# sdr_3157.net
KiCad netlist of a schematic drawn in EAGLE
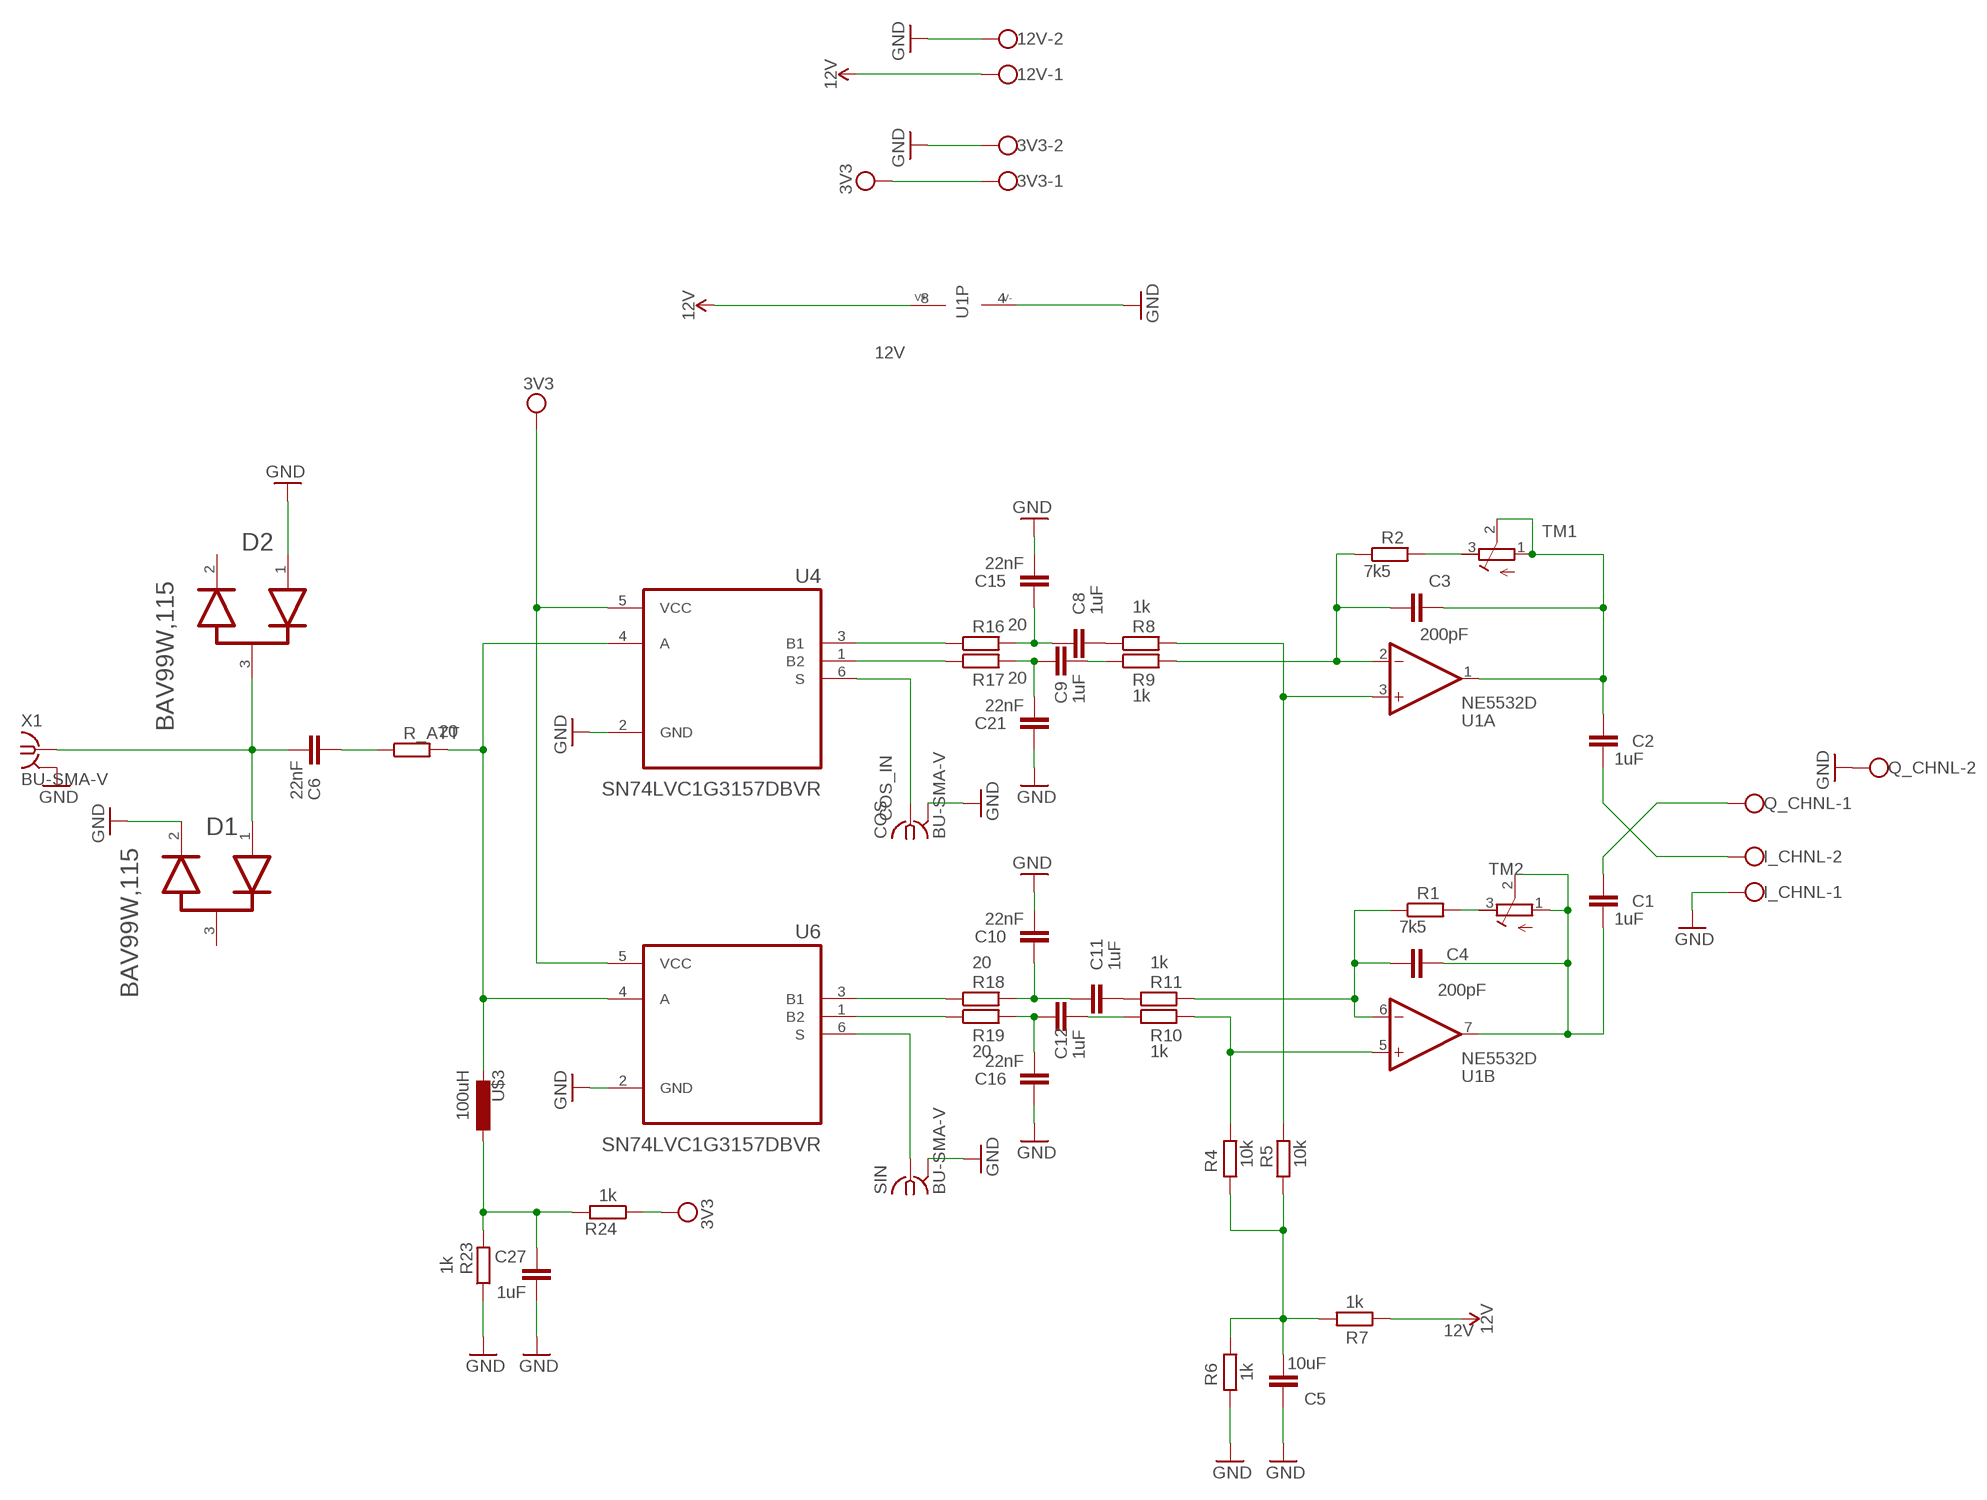
[diagram p0: schematic, sheet 1]

(export (version "E")
  (design (tool "Eeschema 10.0.6"))
  (components
    (comp (ref "3V3")
      (value "W237-102")
      (footprint "eagle-import:W237-102")
      (fields (field (name "MPN") "237-102"))
      (libsource (lib "eagle-import") (part "W237-102"))
    )
    (comp (ref "12V")
      (value "W237-102")
      (footprint "eagle-import:W237-102")
      (fields (field (name "MPN") "237-102"))
      (libsource (lib "eagle-import") (part "W237-102"))
    )
    (comp (ref "C1")
      (value "1uF")
      (footprint "eagle-import:C050-045X075")
      (libsource (lib "eagle-import") (part "C-EU050-045X075"))
    )
    (comp (ref "C2")
      (value "1uF")
      (footprint "eagle-import:C050-045X075")
      (libsource (lib "eagle-import") (part "C-EU050-045X075"))
    )
    (comp (ref "C3")
      (value "200pF")
      (footprint "eagle-import:C050-045X075")
      (libsource (lib "eagle-import") (part "C-EU050-045X075"))
    )
    (comp (ref "C4")
      (value "200pF")
      (footprint "eagle-import:C050-045X075")
      (libsource (lib "eagle-import") (part "C-EU050-045X075"))
    )
    (comp (ref "C5")
      (value "10uF")
      (footprint "eagle-import:C0805")
      (libsource (lib "eagle-import") (part "C-EUC0805"))
    )
    (comp (ref "C6")
      (value "22nF")
      (footprint "eagle-import:C1206K")
      (libsource (lib "eagle-import") (part "C-EUC1206K"))
    )
    (comp (ref "C8")
      (value "1uF")
      (footprint "eagle-import:C0805")
      (libsource (lib "eagle-import") (part "C-EUC0805"))
    )
    (comp (ref "C9")
      (value "1uF")
      (footprint "eagle-import:C0805")
      (libsource (lib "eagle-import") (part "C-EUC0805"))
    )
    (comp (ref "C10")
      (value "22nF")
      (footprint "eagle-import:C0805")
      (libsource (lib "eagle-import") (part "C-EUC0805"))
    )
    (comp (ref "C11")
      (value "1uF")
      (footprint "eagle-import:C0805")
      (libsource (lib "eagle-import") (part "C-EUC0805"))
    )
    (comp (ref "C12")
      (value "1uF")
      (footprint "eagle-import:C0805")
      (libsource (lib "eagle-import") (part "C-EUC0805"))
    )
    (comp (ref "C15")
      (value "22nF")
      (footprint "eagle-import:C0805")
      (libsource (lib "eagle-import") (part "C-EUC0805"))
    )
    (comp (ref "C16")
      (value "22nF")
      (footprint "eagle-import:C0805")
      (libsource (lib "eagle-import") (part "C-EUC0805"))
    )
    (comp (ref "C21")
      (value "22nF")
      (footprint "eagle-import:C0805")
      (libsource (lib "eagle-import") (part "C-EUC0805"))
    )
    (comp (ref "C27")
      (value "1uF")
      (footprint "eagle-import:C0805")
      (libsource (lib "eagle-import") (part "C-EUC0805"))
    )
    (comp (ref "COS")
      (value "BU-SMA-V")
      (footprint "eagle-import:BU-SMA-V")
      (libsource (lib "eagle-import") (part "BU-SMA-V"))
    )
    (comp (ref "D1")
      (value "NEXPERIA_BAV99W,115NEXPERIA_BAV99W,115_0_0")
      (footprint "eagle-import:NEXPERIA_BAV99W,115_0")
      (fields
        (field (name "3DS_PART_NUMBER") "412-00001")
        (field (name "DIGIKEY_PART_NUMBER") "1727-2915-1-ND")
        (field (name "MF") "Nexperia")
      )
      (libsource (lib "eagle-import") (part "NEXPERIA_BAV99W,115NEXPERIA_BAV99W,115_0_0"))
    )
    (comp (ref "D2")
      (value "NEXPERIA_BAV99W,115NEXPERIA_BAV99W,115_0_0")
      (footprint "eagle-import:NEXPERIA_BAV99W,115_0")
      (fields
        (field (name "3DS_PART_NUMBER") "412-00001")
        (field (name "DIGIKEY_PART_NUMBER") "1727-2915-1-ND")
        (field (name "MF") "Nexperia")
      )
      (libsource (lib "eagle-import") (part "NEXPERIA_BAV99W,115NEXPERIA_BAV99W,115_0_0"))
    )
    (comp (ref "I_CHNL")
      (value "W237-102")
      (footprint "eagle-import:W237-102")
      (fields (field (name "MPN") "237-102"))
      (libsource (lib "eagle-import") (part "W237-102"))
    )
    (comp (ref "Q_CHNL")
      (value "W237-102")
      (footprint "eagle-import:W237-102")
      (fields (field (name "MPN") "237-102"))
      (libsource (lib "eagle-import") (part "W237-102"))
    )
    (comp (ref "R1")
      (value "7k5")
      (footprint "eagle-import:R0805")
      (libsource (lib "eagle-import") (part "R-EU_R0805"))
    )
    (comp (ref "R2")
      (value "7k5")
      (footprint "eagle-import:R0805")
      (libsource (lib "eagle-import") (part "R-EU_R0805"))
    )
    (comp (ref "R4")
      (value "10k")
      (footprint "eagle-import:M0805")
      (libsource (lib "eagle-import") (part "R-EU_M0805"))
    )
    (comp (ref "R5")
      (value "10k")
      (footprint "eagle-import:R0805")
      (libsource (lib "eagle-import") (part "R-EU_R0805"))
    )
    (comp (ref "R6")
      (value "1k")
      (footprint "eagle-import:M0805")
      (libsource (lib "eagle-import") (part "R-EU_M0805"))
    )
    (comp (ref "R7")
      (value "1k")
      (footprint "eagle-import:M0805")
      (libsource (lib "eagle-import") (part "R-EU_M0805"))
    )
    (comp (ref "R8")
      (value "1k")
      (footprint "eagle-import:R0805")
      (libsource (lib "eagle-import") (part "R-EU_R0805"))
    )
    (comp (ref "R9")
      (value "1k")
      (footprint "eagle-import:R0805")
      (libsource (lib "eagle-import") (part "R-EU_R0805"))
    )
    (comp (ref "R10")
      (value "1k")
      (footprint "eagle-import:R0805")
      (libsource (lib "eagle-import") (part "R-EU_R0805"))
    )
    (comp (ref "R11")
      (value "1k")
      (footprint "eagle-import:M0805")
      (libsource (lib "eagle-import") (part "R-EU_M0805"))
    )
    (comp (ref "R16")
      (value "20")
      (footprint "eagle-import:R0805")
      (libsource (lib "eagle-import") (part "R-EU_R0805"))
    )
    (comp (ref "R17")
      (value "20")
      (footprint "eagle-import:R0805")
      (libsource (lib "eagle-import") (part "R-EU_R0805"))
    )
    (comp (ref "R18")
      (value "20")
      (footprint "eagle-import:R0805")
      (libsource (lib "eagle-import") (part "R-EU_R0805"))
    )
    (comp (ref "R19")
      (value "20")
      (footprint "eagle-import:R0805")
      (libsource (lib "eagle-import") (part "R-EU_R0805"))
    )
    (comp (ref "R23")
      (value "1k")
      (footprint "eagle-import:R0805")
      (libsource (lib "eagle-import") (part "R-EU_R0805"))
    )
    (comp (ref "R24")
      (value "1k")
      (footprint "eagle-import:R0805")
      (libsource (lib "eagle-import") (part "R-EU_R0805"))
    )
    (comp (ref "R_ATT")
      (value "20")
      (footprint "eagle-import:R1210")
      (libsource (lib "eagle-import") (part "R-EU_R1210"))
    )
    (comp (ref "SIN")
      (value "BU-SMA-V")
      (footprint "eagle-import:BU-SMA-V")
      (libsource (lib "eagle-import") (part "BU-SMA-V"))
    )
    (comp (ref "TM1")
      (value "5k")
      (footprint "eagle-import:RTRIM3296W")
      (libsource (lib "eagle-import") (part "R-TRIMM3296W"))
    )
    (comp (ref "TM2")
      (value "5k")
      (footprint "eagle-import:RTRIM3296W")
      (libsource (lib "eagle-import") (part "R-TRIMM3296W"))
    )
    (comp (ref "U$3")
      (value "100uH")
      (footprint "eagle-import:0207_10")
      (libsource (lib "eagle-import") (part "L-EU0207/10"))
    )
    (comp (ref "U1")
      (value "NE5532D")
      (footprint "eagle-import:SO08")
      (libsource (lib "eagle-import") (part "NE5532D"))
    )
    (comp (ref "U4")
      (value "SN74LVC1G3157DBVR")
      (footprint "eagle-import:SOT95P280X145-6N")
      (fields (field (name "MF") "Texas Instruments"))
      (libsource (lib "eagle-import") (part "SN74LVC1G3157DBVR"))
    )
    (comp (ref "U6")
      (value "SN74LVC1G3157DBVR")
      (footprint "eagle-import:SOT95P280X145-6N")
      (fields (field (name "MF") "Texas Instruments"))
      (libsource (lib "eagle-import") (part "SN74LVC1G3157DBVR"))
    )
    (comp (ref "X1")
      (value "BU-SMA-V")
      (footprint "eagle-import:BU-SMA-V")
      (libsource (lib "eagle-import") (part "BU-SMA-V"))
    )
  )
  (nets
    (net (code "1") (name "/COS_IN") (class "Default")
      (node (ref "COS") (pin "1") (pinfunction "1_1") (pintype "passive"))
      (node (ref "U4") (pin "6") (pinfunction "S_6") (pintype "input"))
    )
    (net (code "2") (name "3V3") (class "Default")
      (node (ref "3V3") (pin "1") (pinfunction "KL_1") (pintype "passive"))
      (node (ref "R24") (pin "1") (pinfunction "1_1") (pintype "passive"))
      (node (ref "U4") (pin "5") (pinfunction "VCC_5") (pintype "power_in"))
      (node (ref "U6") (pin "5") (pinfunction "VCC_5") (pintype "power_in"))
    )
    (net (code "3") (name "12V") (class "Default")
      (node (ref "12V") (pin "1") (pinfunction "KL_1") (pintype "passive"))
      (node (ref "R7") (pin "1") (pinfunction "1_1") (pintype "passive"))
      (node (ref "U1") (pin "8") (pinfunction "V+_8") (pintype "power_in"))
    )
    (net (code "4") (name "GND") (class "Default")
      (node (ref "12V") (pin "2") (pinfunction "KL_2") (pintype "passive"))
      (node (ref "3V3") (pin "2") (pinfunction "KL_2") (pintype "passive"))
      (node (ref "C10") (pin "2") (pinfunction "2_2") (pintype "passive"))
      (node (ref "C15") (pin "2") (pinfunction "2_2") (pintype "passive"))
      (node (ref "C16") (pin "1") (pinfunction "1_1") (pintype "passive"))
      (node (ref "C21") (pin "1") (pinfunction "1_1") (pintype "passive"))
      (node (ref "C27") (pin "1") (pinfunction "1_1") (pintype "passive"))
      (node (ref "C5") (pin "1") (pinfunction "1_1") (pintype "passive"))
      (node (ref "COS") (pin "2") (pinfunction "2_2") (pintype "passive"))
      (node (ref "COS") (pin "3") (pinfunction "2_3") (pintype "passive"))
      (node (ref "COS") (pin "4") (pinfunction "2_4") (pintype "passive"))
      (node (ref "COS") (pin "5") (pinfunction "2_5") (pintype "passive"))
      (node (ref "D1") (pin "2") (pinfunction "2_CATHODE_2") (pintype "passive"))
      (node (ref "D2") (pin "1") (pinfunction "1_ANODE_1") (pintype "passive"))
      (node (ref "I_CHNL") (pin "1") (pinfunction "KL_1") (pintype "passive"))
      (node (ref "Q_CHNL") (pin "2") (pinfunction "KL_2") (pintype "passive"))
      (node (ref "R23") (pin "1") (pinfunction "1_1") (pintype "passive"))
      (node (ref "R6") (pin "1") (pinfunction "1_1") (pintype "passive"))
      (node (ref "SIN") (pin "2") (pinfunction "2_2") (pintype "passive"))
      (node (ref "SIN") (pin "3") (pinfunction "2_3") (pintype "passive"))
      (node (ref "SIN") (pin "4") (pinfunction "2_4") (pintype "passive"))
      (node (ref "SIN") (pin "5") (pinfunction "2_5") (pintype "passive"))
      (node (ref "U1") (pin "4") (pinfunction "V-_4") (pintype "power_in"))
      (node (ref "U4") (pin "2") (pinfunction "GND_2") (pintype "power_in"))
      (node (ref "U6") (pin "2") (pinfunction "GND_2") (pintype "power_in"))
      (node (ref "X1") (pin "2") (pinfunction "2_2") (pintype "passive"))
      (node (ref "X1") (pin "3") (pinfunction "2_3") (pintype "passive"))
      (node (ref "X1") (pin "4") (pinfunction "2_4") (pintype "passive"))
      (node (ref "X1") (pin "5") (pinfunction "2_5") (pintype "passive"))
    )
    (net (code "5") (name "Net-(C5-Pad2)") (class "Default")
      (node (ref "C5") (pin "2") (pinfunction "2_2") (pintype "passive"))
      (node (ref "R4") (pin "1") (pinfunction "1_1") (pintype "passive"))
      (node (ref "R5") (pin "1") (pinfunction "1_1") (pintype "passive"))
      (node (ref "R6") (pin "2") (pinfunction "2_2") (pintype "passive"))
      (node (ref "R7") (pin "2") (pinfunction "2_2") (pintype "passive"))
    )
    (net (code "6") (name "Net-(C6-Pad1)") (class "Default")
      (node (ref "C6") (pin "1") (pinfunction "1_1") (pintype "passive"))
      (node (ref "R_ATT") (pin "1") (pinfunction "1_1") (pintype "passive"))
    )
    (net (code "7") (name "Net-(C8-Pad2)") (class "Default")
      (node (ref "C8") (pin "2") (pinfunction "2_2") (pintype "passive"))
      (node (ref "R8") (pin "1") (pinfunction "1_1") (pintype "passive"))
    )
    (net (code "8") (name "Net-(C9-Pad2)") (class "Default")
      (node (ref "C9") (pin "2") (pinfunction "2_2") (pintype "passive"))
      (node (ref "R9") (pin "1") (pinfunction "1_1") (pintype "passive"))
    )
    (net (code "9") (name "Net-(C10-Pad1)") (class "Default")
      (node (ref "C10") (pin "1") (pinfunction "1_1") (pintype "passive"))
      (node (ref "C11") (pin "1") (pinfunction "1_1") (pintype "passive"))
      (node (ref "R18") (pin "2") (pinfunction "2_2") (pintype "passive"))
    )
    (net (code "10") (name "Net-(C11-Pad2)") (class "Default")
      (node (ref "C11") (pin "2") (pinfunction "2_2") (pintype "passive"))
      (node (ref "R11") (pin "1") (pinfunction "1_1") (pintype "passive"))
    )
    (net (code "11") (name "Net-(C12-Pad1)") (class "Default")
      (node (ref "C12") (pin "1") (pinfunction "1_1") (pintype "passive"))
      (node (ref "C16") (pin "2") (pinfunction "2_2") (pintype "passive"))
      (node (ref "R19") (pin "2") (pinfunction "2_2") (pintype "passive"))
    )
    (net (code "12") (name "Net-(C12-Pad2)") (class "Default")
      (node (ref "C12") (pin "2") (pinfunction "2_2") (pintype "passive"))
      (node (ref "R10") (pin "1") (pinfunction "1_1") (pintype "passive"))
    )
    (net (code "13") (name "Net-(C15-Pad1)") (class "Default")
      (node (ref "C15") (pin "1") (pinfunction "1_1") (pintype "passive"))
      (node (ref "C8") (pin "1") (pinfunction "1_1") (pintype "passive"))
      (node (ref "R16") (pin "2") (pinfunction "2_2") (pintype "passive"))
    )
    (net (code "14") (name "Net-(C21-Pad2)") (class "Default")
      (node (ref "C21") (pin "2") (pinfunction "2_2") (pintype "passive"))
      (node (ref "C9") (pin "1") (pinfunction "1_1") (pintype "passive"))
      (node (ref "R17") (pin "2") (pinfunction "2_2") (pintype "passive"))
    )
    (net (code "15") (name "Net-(C27-Pad2)") (class "Default")
      (node (ref "C27") (pin "2") (pinfunction "2_2") (pintype "passive"))
      (node (ref "R23") (pin "2") (pinfunction "2_2") (pintype "passive"))
      (node (ref "R24") (pin "2") (pinfunction "2_2") (pintype "passive"))
      (node (ref "U$3") (pin "1") (pinfunction "1_1") (pintype "passive"))
    )
    (net (code "16") (name "Net-(D1-1_ANODE)") (class "Default")
      (node (ref "C6") (pin "2") (pinfunction "2_2") (pintype "passive"))
      (node (ref "D1") (pin "1") (pinfunction "1_ANODE_1") (pintype "passive"))
      (node (ref "D2") (pin "3") (pinfunction "1_CATHODE/2_ANODE_3") (pintype "passive"))
      (node (ref "X1") (pin "1") (pinfunction "1_1") (pintype "passive"))
    )
    (net (code "17") (name "Net-(I_CHNLB-KL)") (class "Default")
      (node (ref "C2") (pin "2") (pinfunction "2_2") (pintype "passive"))
      (node (ref "I_CHNL") (pin "2") (pinfunction "KL_2") (pintype "passive"))
    )
    (net (code "18") (name "Net-(Q_CHNLA-KL)") (class "Default")
      (node (ref "C1") (pin "1") (pinfunction "1_1") (pintype "passive"))
      (node (ref "Q_CHNL") (pin "1") (pinfunction "KL_1") (pintype "passive"))
    )
    (net (code "19") (name "Net-(TM1-A)") (class "Default")
      (node (ref "C2") (pin "1") (pinfunction "1_1") (pintype "passive"))
      (node (ref "C3") (pin "2") (pinfunction "2_2") (pintype "passive"))
      (node (ref "TM1") (pin "1") (pinfunction "A_1") (pintype "passive"))
      (node (ref "TM1") (pin "2") (pinfunction "S_2") (pintype "passive"))
      (node (ref "U1") (pin "1") (pinfunction "OUT_1") (pintype "output"))
    )
    (net (code "20") (name "Net-(TM1-E)") (class "Default")
      (node (ref "R2") (pin "2") (pinfunction "2_2") (pintype "passive"))
      (node (ref "TM1") (pin "3") (pinfunction "E_3") (pintype "passive"))
    )
    (net (code "21") (name "Net-(TM2-A)") (class "Default")
      (node (ref "C1") (pin "2") (pinfunction "2_2") (pintype "passive"))
      (node (ref "C4") (pin "2") (pinfunction "2_2") (pintype "passive"))
      (node (ref "TM2") (pin "1") (pinfunction "A_1") (pintype "passive"))
      (node (ref "TM2") (pin "2") (pinfunction "S_2") (pintype "passive"))
      (node (ref "U1") (pin "7") (pinfunction "OUT_7") (pintype "output"))
    )
    (net (code "22") (name "Net-(TM2-E)") (class "Default")
      (node (ref "R1") (pin "2") (pinfunction "2_2") (pintype "passive"))
      (node (ref "TM2") (pin "3") (pinfunction "E_3") (pintype "passive"))
    )
    (net (code "23") (name "Net-(U1A-+IN)") (class "Default")
      (node (ref "R5") (pin "2") (pinfunction "2_2") (pintype "passive"))
      (node (ref "R8") (pin "2") (pinfunction "2_2") (pintype "passive"))
      (node (ref "U1") (pin "3") (pinfunction "+IN_3") (pintype "input"))
    )
    (net (code "24") (name "Net-(U1A--IN)") (class "Default")
      (node (ref "C3") (pin "1") (pinfunction "1_1") (pintype "passive"))
      (node (ref "R2") (pin "1") (pinfunction "1_1") (pintype "passive"))
      (node (ref "R9") (pin "2") (pinfunction "2_2") (pintype "passive"))
      (node (ref "U1") (pin "2") (pinfunction "-IN_2") (pintype "input"))
    )
    (net (code "25") (name "Net-(U1B-+IN)") (class "Default")
      (node (ref "R10") (pin "2") (pinfunction "2_2") (pintype "passive"))
      (node (ref "R4") (pin "2") (pinfunction "2_2") (pintype "passive"))
      (node (ref "U1") (pin "5") (pinfunction "+IN_5") (pintype "input"))
    )
    (net (code "26") (name "Net-(U1B--IN)") (class "Default")
      (node (ref "C4") (pin "1") (pinfunction "1_1") (pintype "passive"))
      (node (ref "R1") (pin "1") (pinfunction "1_1") (pintype "passive"))
      (node (ref "R11") (pin "2") (pinfunction "2_2") (pintype "passive"))
      (node (ref "U1") (pin "6") (pinfunction "-IN_6") (pintype "input"))
    )
    (net (code "27") (name "Net-(U4-A)") (class "Default")
      (node (ref "R_ATT") (pin "2") (pinfunction "2_2") (pintype "passive"))
      (node (ref "U$3") (pin "2") (pinfunction "2_2") (pintype "passive"))
      (node (ref "U4") (pin "4") (pinfunction "A_4") (pintype "output"))
      (node (ref "U6") (pin "4") (pinfunction "A_4") (pintype "output"))
    )
    (net (code "28") (name "Net-(U4-B1)") (class "Default")
      (node (ref "R16") (pin "1") (pinfunction "1_1") (pintype "passive"))
      (node (ref "U4") (pin "3") (pinfunction "B1_3") (pintype "input"))
    )
    (net (code "29") (name "Net-(U4-B2)") (class "Default")
      (node (ref "R17") (pin "1") (pinfunction "1_1") (pintype "passive"))
      (node (ref "U4") (pin "1") (pinfunction "B2_1") (pintype "input"))
    )
    (net (code "30") (name "Net-(U6-B1)") (class "Default")
      (node (ref "R18") (pin "1") (pinfunction "1_1") (pintype "passive"))
      (node (ref "U6") (pin "3") (pinfunction "B1_3") (pintype "input"))
    )
    (net (code "31") (name "Net-(U6-B2)") (class "Default")
      (node (ref "R19") (pin "1") (pinfunction "1_1") (pintype "passive"))
      (node (ref "U6") (pin "1") (pinfunction "B2_1") (pintype "input"))
    )
    (net (code "32") (name "Net-(U6-S)") (class "Default")
      (node (ref "SIN") (pin "1") (pinfunction "1_1") (pintype "passive"))
      (node (ref "U6") (pin "6") (pinfunction "S_6") (pintype "input"))
    )
    (net (code "33") (name "unconnected-(D1-1_CATHODE{slash}2_ANODE-Pad3)") (class "Default")
      (node (ref "D1") (pin "3") (pinfunction "1_CATHODE/2_ANODE_3") (pintype "passive"))
    )
    (net (code "34") (name "unconnected-(D2-2_CATHODE-Pad2)") (class "Default")
      (node (ref "D2") (pin "2") (pinfunction "2_CATHODE_2") (pintype "passive"))
    )
  )
)
